# Power.net
KiCad netlist of a schematic drawn in Altium Designer
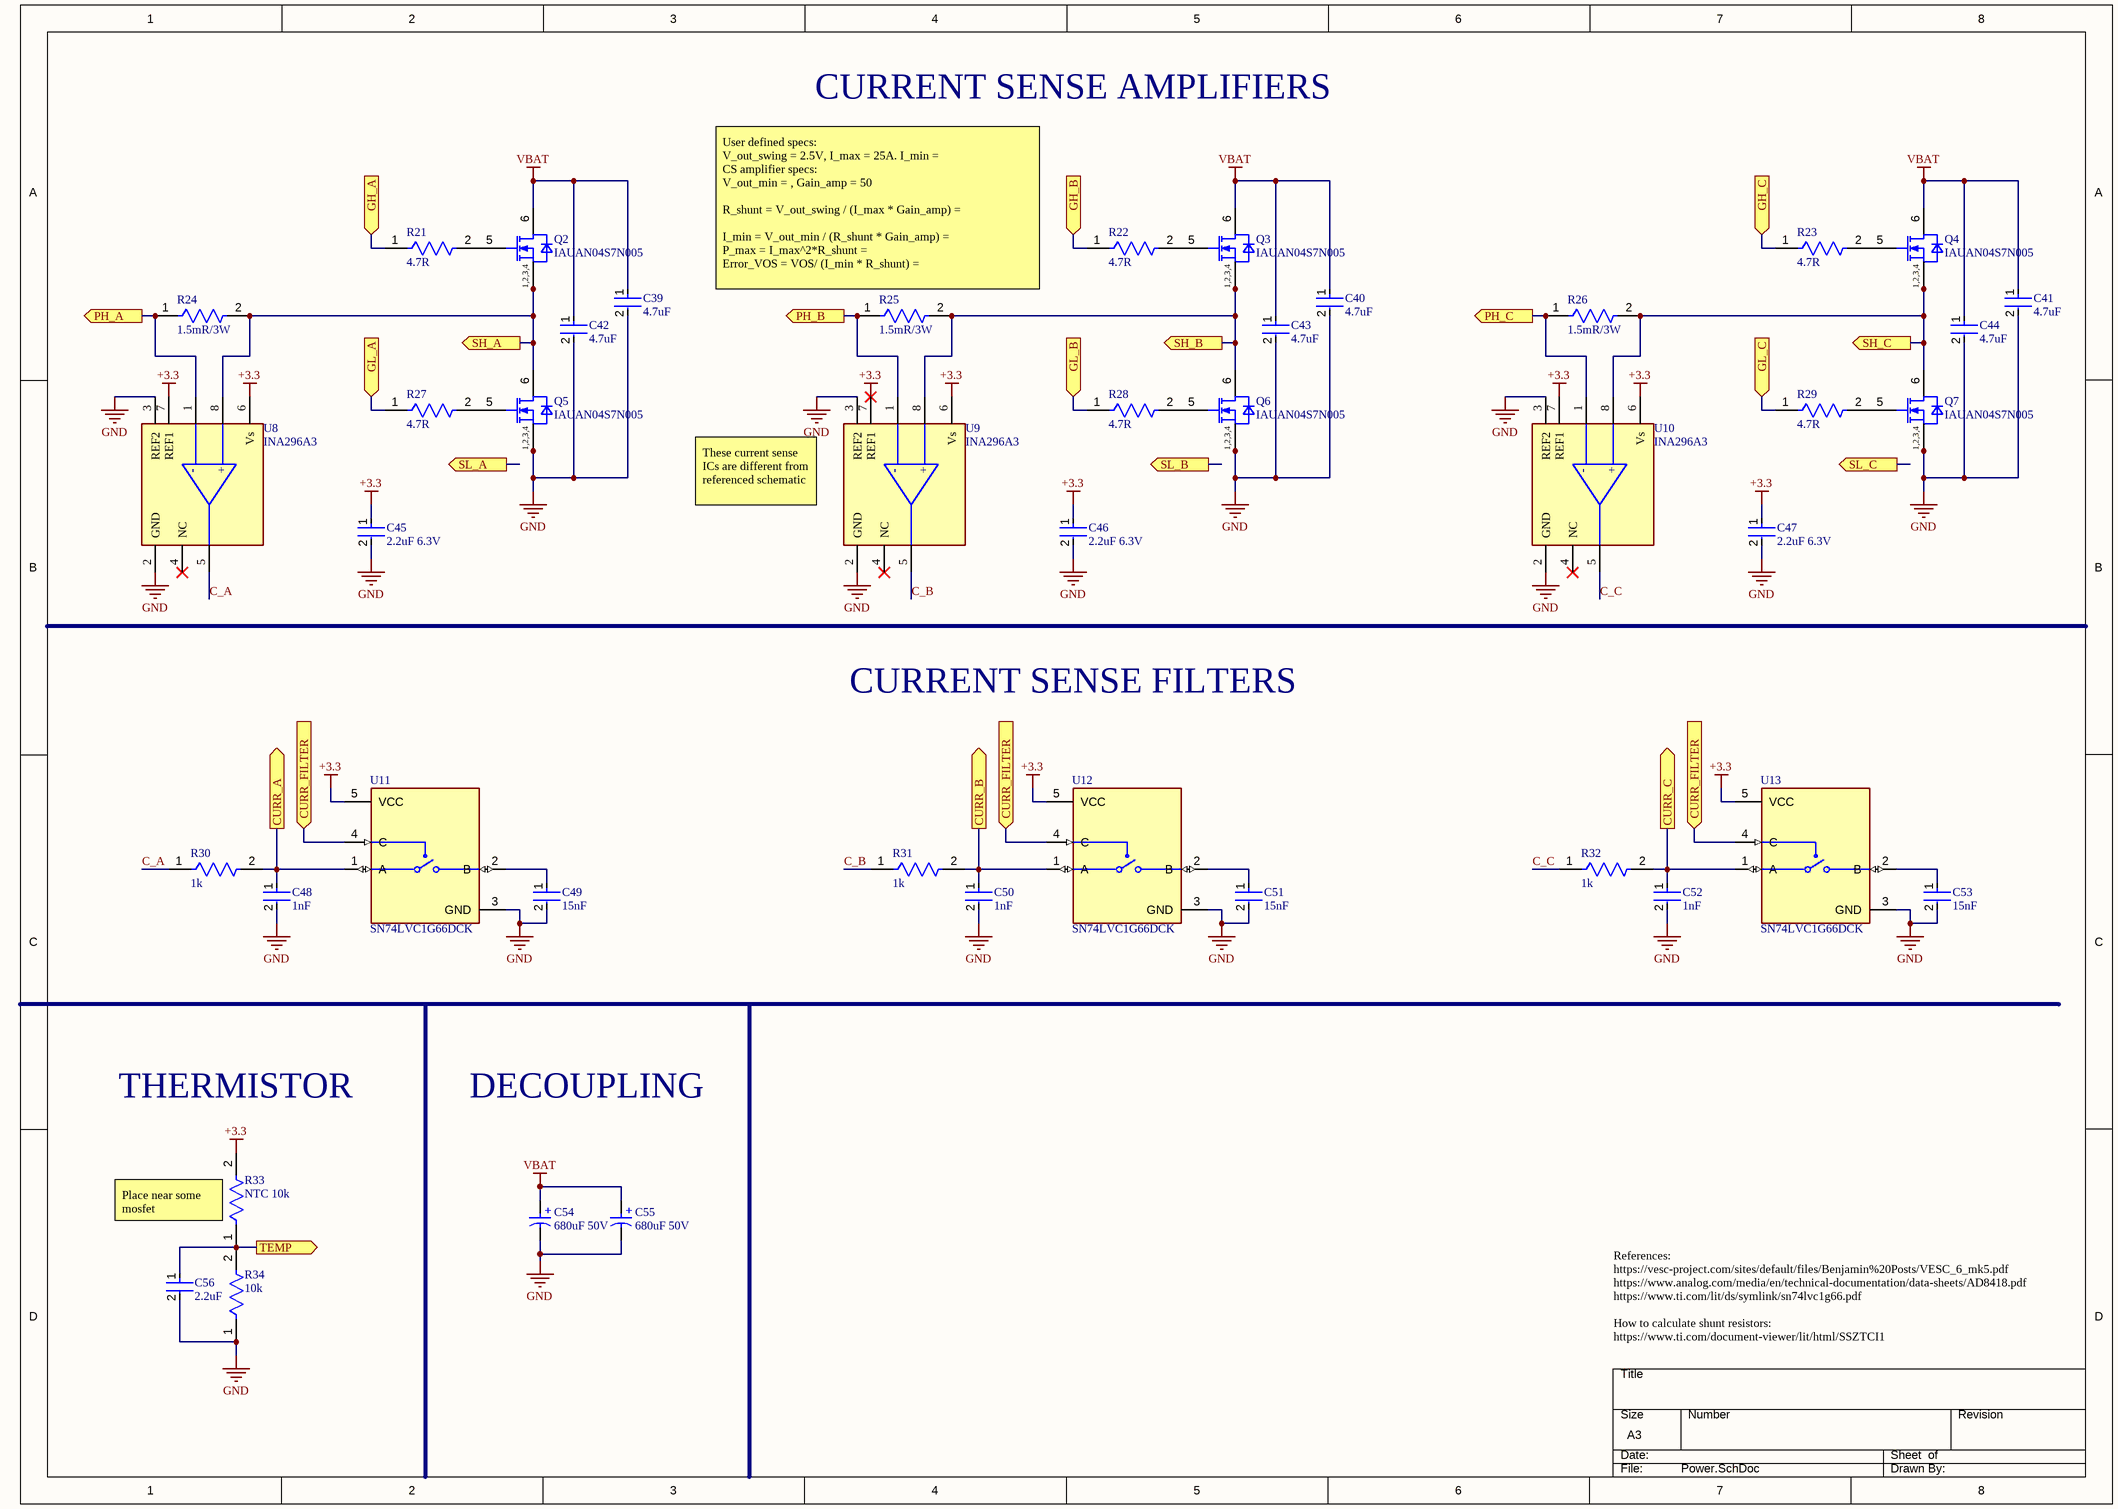
[diagram p0: Power.SchDoc]

(export (version "E")
  (design (tool "Eeschema 10.0.6"))
  (components
    (comp (ref "C39")
      (value "4.7uF")
      (footprint "FP-CC0805-0_85-MFG")
      (description "4.7uF 50V X7R ±10% 0805 Multilayer Ceramic Capacitors MLCC - SMD/SMT ROHS")
      (fields
        (field (name "MANUFACTURER") "Yageo Group")
        (field (name "MANUFACTURER PART NUMBER") "CC0402KRX7R9BB682")
      )
      (libsource (lib "BEESC_Lib") (part "0805B475K500NT"))
    )
    (comp (ref "C40")
      (value "4.7uF")
      (footprint "FP-CC0805-0_85-MFG")
      (description "4.7uF 50V X7R ±10% 0805 Multilayer Ceramic Capacitors MLCC - SMD/SMT ROHS")
      (fields
        (field (name "MANUFACTURER") "Yageo Group")
        (field (name "MANUFACTURER PART NUMBER") "CC0402KRX7R9BB682")
      )
      (libsource (lib "BEESC_Lib") (part "0805B475K500NT"))
    )
    (comp (ref "C41")
      (value "4.7uF")
      (footprint "FP-CC0805-0_85-MFG")
      (description "4.7uF 50V X7R ±10% 0805 Multilayer Ceramic Capacitors MLCC - SMD/SMT ROHS")
      (fields
        (field (name "MANUFACTURER") "Yageo Group")
        (field (name "MANUFACTURER PART NUMBER") "CC0402KRX7R9BB682")
      )
      (libsource (lib "BEESC_Lib") (part "0805B475K500NT"))
    )
    (comp (ref "C42")
      (value "4.7uF")
      (footprint "FP-CC0805-0_85-MFG")
      (description "4.7uF 50V X7R ±10% 0805 Multilayer Ceramic Capacitors MLCC - SMD/SMT ROHS")
      (fields
        (field (name "MANUFACTURER") "Yageo Group")
        (field (name "MANUFACTURER PART NUMBER") "CC0402KRX7R9BB682")
      )
      (libsource (lib "BEESC_Lib") (part "0805B475K500NT"))
    )
    (comp (ref "C43")
      (value "4.7uF")
      (footprint "FP-CC0805-0_85-MFG")
      (description "4.7uF 50V X7R ±10% 0805 Multilayer Ceramic Capacitors MLCC - SMD/SMT ROHS")
      (fields
        (field (name "MANUFACTURER") "Yageo Group")
        (field (name "MANUFACTURER PART NUMBER") "CC0402KRX7R9BB682")
      )
      (libsource (lib "BEESC_Lib") (part "0805B475K500NT"))
    )
    (comp (ref "C44")
      (value "4.7uF")
      (footprint "FP-CC0805-0_85-MFG")
      (description "4.7uF 50V X7R ±10% 0805 Multilayer Ceramic Capacitors MLCC - SMD/SMT ROHS")
      (fields
        (field (name "MANUFACTURER") "Yageo Group")
        (field (name "MANUFACTURER PART NUMBER") "CC0402KRX7R9BB682")
      )
      (libsource (lib "BEESC_Lib") (part "0805B475K500NT"))
    )
    (comp (ref "C45")
      (value "2.2uF 6.3V")
      (footprint "FP-CC0402-MFG")
      (description "2.2uF 6.3V X5R ±20% 0402 Multilayer Ceramic Capacitors MLCC - SMD/SMT ROHS")
      (fields
        (field (name "MANUFACTURER") "Yageo Group")
        (field (name "MANUFACTURER PART NUMBER") "CC0402KRX7R9BB682")
      )
      (libsource (lib "BEESC_Lib") (part "CL05A225MQ5NSNC"))
    )
    (comp (ref "C46")
      (value "2.2uF 6.3V")
      (footprint "FP-CC0402-MFG")
      (description "2.2uF 6.3V X5R ±20% 0402 Multilayer Ceramic Capacitors MLCC - SMD/SMT ROHS")
      (fields
        (field (name "MANUFACTURER") "Yageo Group")
        (field (name "MANUFACTURER PART NUMBER") "CC0402KRX7R9BB682")
      )
      (libsource (lib "BEESC_Lib") (part "CL05A225MQ5NSNC"))
    )
    (comp (ref "C47")
      (value "2.2uF 6.3V")
      (footprint "FP-CC0402-MFG")
      (description "2.2uF 6.3V X5R ±20% 0402 Multilayer Ceramic Capacitors MLCC - SMD/SMT ROHS")
      (fields
        (field (name "MANUFACTURER") "Yageo Group")
        (field (name "MANUFACTURER PART NUMBER") "CC0402KRX7R9BB682")
      )
      (libsource (lib "BEESC_Lib") (part "CL05A225MQ5NSNC"))
    )
    (comp (ref "C48")
      (value "1nF")
      (footprint "FP-CC0402-MFG")
      (description "1nF 50V X7R ±10% 0402 Multilayer Ceramic Capacitors MLCC - SMD/SMT ROHS")
      (fields
        (field (name "MANUFACTURER") "Yageo Group")
        (field (name "MANUFACTURER PART NUMBER") "CC0402KRX7R9BB682")
      )
      (libsource (lib "BEESC_Lib") (part "0402B102K500NT"))
    )
    (comp (ref "C49")
      (value "15nF")
      (footprint "FP-CC0402-MFG")
      (description "15nF 50V X7R ±10% 0402 Multilayer Ceramic Capacitors MLCC - SMD/SMT ROHS")
      (fields
        (field (name "MANUFACTURER") "Yageo Group")
        (field (name "MANUFACTURER PART NUMBER") "CC0402KRX7R9BB682")
      )
      (libsource (lib "BEESC_Lib") (part "CC0402KRX7R9BB153"))
    )
    (comp (ref "C50")
      (value "1nF")
      (footprint "FP-CC0402-MFG")
      (description "1nF 50V X7R ±10% 0402 Multilayer Ceramic Capacitors MLCC - SMD/SMT ROHS")
      (fields
        (field (name "MANUFACTURER") "Yageo Group")
        (field (name "MANUFACTURER PART NUMBER") "CC0402KRX7R9BB682")
      )
      (libsource (lib "BEESC_Lib") (part "0402B102K500NT"))
    )
    (comp (ref "C51")
      (value "15nF")
      (footprint "FP-CC0402-MFG")
      (description "15nF 50V X7R ±10% 0402 Multilayer Ceramic Capacitors MLCC - SMD/SMT ROHS")
      (fields
        (field (name "MANUFACTURER") "Yageo Group")
        (field (name "MANUFACTURER PART NUMBER") "CC0402KRX7R9BB682")
      )
      (libsource (lib "BEESC_Lib") (part "CC0402KRX7R9BB153"))
    )
    (comp (ref "C52")
      (value "1nF")
      (footprint "FP-CC0402-MFG")
      (description "1nF 50V X7R ±10% 0402 Multilayer Ceramic Capacitors MLCC - SMD/SMT ROHS")
      (fields
        (field (name "MANUFACTURER") "Yageo Group")
        (field (name "MANUFACTURER PART NUMBER") "CC0402KRX7R9BB682")
      )
      (libsource (lib "BEESC_Lib") (part "0402B102K500NT"))
    )
    (comp (ref "C53")
      (value "15nF")
      (footprint "FP-CC0402-MFG")
      (description "15nF 50V X7R ±10% 0402 Multilayer Ceramic Capacitors MLCC - SMD/SMT ROHS")
      (fields
        (field (name "MANUFACTURER") "Yageo Group")
        (field (name "MANUFACTURER PART NUMBER") "CC0402KRX7R9BB682")
      )
      (libsource (lib "BEESC_Lib") (part "CC0402KRX7R9BB153"))
    )
    (comp (ref "C54")
      (value "680uF 50V")
      (footprint "WCAP-ATG5_D13H20_BENT_MIRROR")
      (description "Aluminium Electrolytic Capacitors - Radial Leaded WCAP-ATG5 680uF 50V 20% Radial")
      (libsource (lib "BEESC_Lib") (part "860020678024"))
    )
    (comp (ref "C55")
      (value "680uF 50V")
      (footprint "WCAP-ATG5_D13H20_BENT_MIRROR")
      (description "Aluminium Electrolytic Capacitors - Radial Leaded WCAP-ATG5 680uF 50V 20% Radial")
      (libsource (lib "BEESC_Lib") (part "860020678024"))
    )
    (comp (ref "C56")
      (value "2.2uF")
      (footprint "FP-CC0805-0_85-MFG")
      (description "2.2uF 50V X7R ±10% 0805 Multilayer Ceramic Capacitors MLCC - SMD/SMT ROHS")
      (fields
        (field (name "MANUFACTURER") "Yageo Group")
        (field (name "MANUFACTURER PART NUMBER") "CC0402KRX7R9BB682")
      )
      (libsource (lib "BEESC_Lib") (part "CC0805KKX7R9BB225"))
    )
    (comp (ref "Q2")
      (value "IAUAN04S7N005")
      (footprint "IFX-PG-HSOF-5-1-V")
      (fields (field (name "MANUFACTURER") "Infineon Technologies"))
      (libsource (lib "BEESC_Lib") (part "IAUAN04S7N005"))
    )
    (comp (ref "Q3")
      (value "IAUAN04S7N005")
      (footprint "IFX-PG-HSOF-5-1-V")
      (fields (field (name "MANUFACTURER") "Infineon Technologies"))
      (libsource (lib "BEESC_Lib") (part "IAUAN04S7N005"))
    )
    (comp (ref "Q4")
      (value "IAUAN04S7N005")
      (footprint "IFX-PG-HSOF-5-1-V")
      (fields (field (name "MANUFACTURER") "Infineon Technologies"))
      (libsource (lib "BEESC_Lib") (part "IAUAN04S7N005"))
    )
    (comp (ref "Q5")
      (value "IAUAN04S7N005")
      (footprint "IFX-PG-HSOF-5-1-V")
      (fields (field (name "MANUFACTURER") "Infineon Technologies"))
      (libsource (lib "BEESC_Lib") (part "IAUAN04S7N005"))
    )
    (comp (ref "Q6")
      (value "IAUAN04S7N005")
      (footprint "IFX-PG-HSOF-5-1-V")
      (fields (field (name "MANUFACTURER") "Infineon Technologies"))
      (libsource (lib "BEESC_Lib") (part "IAUAN04S7N005"))
    )
    (comp (ref "Q7")
      (value "IAUAN04S7N005")
      (footprint "IFX-PG-HSOF-5-1-V")
      (fields (field (name "MANUFACTURER") "Infineon Technologies"))
      (libsource (lib "BEESC_Lib") (part "IAUAN04S7N005"))
    )
    (comp (ref "R21")
      (value "4.7R")
      (footprint "FP-AC0402-MFG")
      (libsource (lib "BEESC_Lib") (part "0402WGF470KTCE"))
    )
    (comp (ref "R22")
      (value "4.7R")
      (footprint "FP-AC0402-MFG")
      (libsource (lib "BEESC_Lib") (part "0402WGF470KTCE"))
    )
    (comp (ref "R23")
      (value "4.7R")
      (footprint "FP-AC0402-MFG")
      (libsource (lib "BEESC_Lib") (part "0402WGF470KTCE"))
    )
    (comp (ref "R24")
      (value "1.5mR/3W")
      (footprint "FP-AC2512-MFG")
      (libsource (lib "BEESC_Lib") (part "HoCGX2512-3W-1.5mR-1%"))
    )
    (comp (ref "R25")
      (value "1.5mR/3W")
      (footprint "FP-AC2512-MFG")
      (libsource (lib "BEESC_Lib") (part "HoCGX2512-3W-1.5mR-1%"))
    )
    (comp (ref "R26")
      (value "1.5mR/3W")
      (footprint "FP-AC2512-MFG")
      (libsource (lib "BEESC_Lib") (part "HoCGX2512-3W-1.5mR-1%"))
    )
    (comp (ref "R27")
      (value "4.7R")
      (footprint "FP-AC0402-MFG")
      (libsource (lib "BEESC_Lib") (part "0402WGF470KTCE"))
    )
    (comp (ref "R28")
      (value "4.7R")
      (footprint "FP-AC0402-MFG")
      (libsource (lib "BEESC_Lib") (part "0402WGF470KTCE"))
    )
    (comp (ref "R29")
      (value "4.7R")
      (footprint "FP-AC0402-MFG")
      (libsource (lib "BEESC_Lib") (part "0402WGF470KTCE"))
    )
    (comp (ref "R30")
      (value "1k")
      (footprint "FP-AC0402-MFG")
      (libsource (lib "BEESC_Lib") (part "0402WGF1001TCE"))
    )
    (comp (ref "R31")
      (value "1k")
      (footprint "FP-AC0402-MFG")
      (libsource (lib "BEESC_Lib") (part "0402WGF1001TCE"))
    )
    (comp (ref "R32")
      (value "1k")
      (footprint "FP-AC0402-MFG")
      (libsource (lib "BEESC_Lib") (part "0402WGF1001TCE"))
    )
    (comp (ref "R33")
      (value "NTC 10k")
      (footprint "FP-AC0402-MFG")
      (description "-40℃~+125℃ 0.5mm 100mW 10kΩ 1mW/℃ 1mm 310uA 3380K 3434K 3455K ±1% ±1% 0402 NTC Thermistors ROHS")
      (libsource (lib "BEESC_Lib") (part "NCP15XH103F03RC"))
    )
    (comp (ref "R34")
      (value "10k")
      (footprint "FP-AC0402-MFG")
      (libsource (lib "BEESC_Lib") (part "0402WGF1002TCE"))
    )
    (comp (ref "U8")
      (value "INA296A3")
      (footprint "FP-DDF0008A-MFG")
      (libsource (lib "BEESC_Lib") (part "INA296A3IDDFR"))
    )
    (comp (ref "U9")
      (value "INA296A3")
      (footprint "FP-DDF0008A-MFG")
      (libsource (lib "BEESC_Lib") (part "INA296A3IDDFR"))
    )
    (comp (ref "U10")
      (value "INA296A3")
      (footprint "FP-DDF0008A-MFG")
      (libsource (lib "BEESC_Lib") (part "INA296A3IDDFR"))
    )
    (comp (ref "U11")
      (value "SN74LVC1G66DCK")
      (footprint "FP-DCK0005A-MFG")
      (libsource (lib "BEESC_Lib") (part "SN74LVC1G66DCKR"))
    )
    (comp (ref "U12")
      (value "SN74LVC1G66DCK")
      (footprint "FP-DCK0005A-MFG")
      (libsource (lib "BEESC_Lib") (part "SN74LVC1G66DCKR"))
    )
    (comp (ref "U13")
      (value "SN74LVC1G66DCK")
      (footprint "FP-DCK0005A-MFG")
      (libsource (lib "BEESC_Lib") (part "SN74LVC1G66DCKR"))
    )
  )
  (nets
    (net (code "1") (name "+3.3") (class "Default")
      (node (ref "C45") (pin "1") (pinfunction "1_1") (pintype "passive"))
      (node (ref "C46") (pin "1") (pinfunction "1_1") (pintype "passive"))
      (node (ref "C47") (pin "1") (pinfunction "1_1") (pintype "passive"))
      (node (ref "R33") (pin "2") (pinfunction "2_2") (pintype "passive"))
      (node (ref "U10") (pin "6") (pinfunction "Vs_6") (pintype "power_in"))
      (node (ref "U10") (pin "7") (pinfunction "REF1_7") (pintype "passive"))
      (node (ref "U11") (pin "5") (pinfunction "VCC_5") (pintype "power_in"))
      (node (ref "U12") (pin "5") (pinfunction "VCC_5") (pintype "power_in"))
      (node (ref "U13") (pin "5") (pinfunction "VCC_5") (pintype "power_in"))
      (node (ref "U8") (pin "6") (pinfunction "Vs_6") (pintype "power_in"))
      (node (ref "U8") (pin "7") (pinfunction "REF1_7") (pintype "passive"))
      (node (ref "U9") (pin "6") (pinfunction "Vs_6") (pintype "power_in"))
      (node (ref "U9") (pin "7") (pinfunction "REF1_7") (pintype "passive"))
    )
    (net (code "2") (name "/CURR_A") (class "Default")
      (node (ref "C48") (pin "1") (pinfunction "1_1") (pintype "passive"))
      (node (ref "R30") (pin "2") (pinfunction "2_2") (pintype "passive"))
      (node (ref "U11") (pin "1") (pinfunction "A_1") (pintype "bidirectional"))
    )
    (net (code "3") (name "/CURR_B") (class "Default")
      (node (ref "C50") (pin "1") (pinfunction "1_1") (pintype "passive"))
      (node (ref "R31") (pin "2") (pinfunction "2_2") (pintype "passive"))
      (node (ref "U12") (pin "1") (pinfunction "A_1") (pintype "bidirectional"))
    )
    (net (code "4") (name "/CURR_C") (class "Default")
      (node (ref "C52") (pin "1") (pinfunction "1_1") (pintype "passive"))
      (node (ref "R32") (pin "2") (pinfunction "2_2") (pintype "passive"))
      (node (ref "U13") (pin "1") (pinfunction "A_1") (pintype "bidirectional"))
    )
    (net (code "5") (name "/CURR_FILTER") (class "Default")
      (node (ref "U11") (pin "4") (pinfunction "C_4") (pintype "input"))
      (node (ref "U12") (pin "4") (pinfunction "C_4") (pintype "input"))
      (node (ref "U13") (pin "4") (pinfunction "C_4") (pintype "input"))
    )
    (net (code "6") (name "/C_A") (class "Default")
      (node (ref "R30") (pin "1") (pinfunction "1_1") (pintype "passive"))
      (node (ref "U8") (pin "5") (pinfunction "OUT_5") (pintype "passive"))
    )
    (net (code "7") (name "/C_B") (class "Default")
      (node (ref "R31") (pin "1") (pinfunction "1_1") (pintype "passive"))
      (node (ref "U9") (pin "5") (pinfunction "OUT_5") (pintype "passive"))
    )
    (net (code "8") (name "/C_C") (class "Default")
      (node (ref "R32") (pin "1") (pinfunction "1_1") (pintype "passive"))
      (node (ref "U10") (pin "5") (pinfunction "OUT_5") (pintype "passive"))
    )
    (net (code "9") (name "/GH_A") (class "Default")
      (node (ref "R21") (pin "1") (pinfunction "1_1") (pintype "passive"))
    )
    (net (code "10") (name "/GH_B") (class "Default")
      (node (ref "R22") (pin "1") (pinfunction "1_1") (pintype "passive"))
    )
    (net (code "11") (name "/GH_C") (class "Default")
      (node (ref "R23") (pin "1") (pinfunction "1_1") (pintype "passive"))
    )
    (net (code "12") (name "/GL_A") (class "Default")
      (node (ref "R27") (pin "1") (pinfunction "1_1") (pintype "passive"))
    )
    (net (code "13") (name "/GL_B") (class "Default")
      (node (ref "R28") (pin "1") (pinfunction "1_1") (pintype "passive"))
    )
    (net (code "14") (name "/GL_C") (class "Default")
      (node (ref "R29") (pin "1") (pinfunction "1_1") (pintype "passive"))
    )
    (net (code "15") (name "/PH_A") (class "Default")
      (node (ref "R24") (pin "1") (pinfunction "1_1") (pintype "passive"))
      (node (ref "U8") (pin "1") (pinfunction "IN-_1") (pintype "tri_state"))
    )
    (net (code "16") (name "/PH_B") (class "Default")
      (node (ref "R25") (pin "1") (pinfunction "1_1") (pintype "passive"))
      (node (ref "U9") (pin "1") (pinfunction "IN-_1") (pintype "tri_state"))
    )
    (net (code "17") (name "/PH_C") (class "Default")
      (node (ref "R26") (pin "1") (pinfunction "1_1") (pintype "passive"))
      (node (ref "U10") (pin "1") (pinfunction "IN-_1") (pintype "tri_state"))
    )
    (net (code "18") (name "/SH_A") (class "Default")
      (node (ref "Q2") (pin "1") (pinfunction "S1_1") (pintype "passive"))
      (node (ref "Q2") (pin "2") (pinfunction "S2_2") (pintype "passive"))
      (node (ref "Q2") (pin "3") (pinfunction "S3_3") (pintype "passive"))
      (node (ref "Q2") (pin "4") (pinfunction "S4_4") (pintype "passive"))
      (node (ref "Q5") (pin "6") (pinfunction "D_6") (pintype "passive"))
      (node (ref "R24") (pin "2") (pinfunction "2_2") (pintype "passive"))
      (node (ref "U8") (pin "8") (pinfunction "IN+_8") (pintype "tri_state"))
    )
    (net (code "19") (name "/SH_B") (class "Default")
      (node (ref "Q3") (pin "1") (pinfunction "S1_1") (pintype "passive"))
      (node (ref "Q3") (pin "2") (pinfunction "S2_2") (pintype "passive"))
      (node (ref "Q3") (pin "3") (pinfunction "S3_3") (pintype "passive"))
      (node (ref "Q3") (pin "4") (pinfunction "S4_4") (pintype "passive"))
      (node (ref "Q6") (pin "6") (pinfunction "D_6") (pintype "passive"))
      (node (ref "R25") (pin "2") (pinfunction "2_2") (pintype "passive"))
      (node (ref "U9") (pin "8") (pinfunction "IN+_8") (pintype "tri_state"))
    )
    (net (code "20") (name "/SH_C") (class "Default")
      (node (ref "Q4") (pin "1") (pinfunction "S1_1") (pintype "passive"))
      (node (ref "Q4") (pin "2") (pinfunction "S2_2") (pintype "passive"))
      (node (ref "Q4") (pin "3") (pinfunction "S3_3") (pintype "passive"))
      (node (ref "Q4") (pin "4") (pinfunction "S4_4") (pintype "passive"))
      (node (ref "Q7") (pin "6") (pinfunction "D_6") (pintype "passive"))
      (node (ref "R26") (pin "2") (pinfunction "2_2") (pintype "passive"))
      (node (ref "U10") (pin "8") (pinfunction "IN+_8") (pintype "tri_state"))
    )
    (net (code "24") (name "/TEMP") (class "Default")
      (node (ref "C56") (pin "1") (pinfunction "1_1") (pintype "passive"))
      (node (ref "R33") (pin "1") (pinfunction "1_1") (pintype "passive"))
      (node (ref "R34") (pin "2") (pinfunction "2_2") (pintype "passive"))
    )
    (net (code "25") (name "GND") (class "Default")
      (node (ref "C39") (pin "2") (pinfunction "2_2") (pintype "passive"))
      (node (ref "C40") (pin "2") (pinfunction "2_2") (pintype "passive"))
      (node (ref "C41") (pin "2") (pinfunction "2_2") (pintype "passive"))
      (node (ref "C42") (pin "2") (pinfunction "2_2") (pintype "passive"))
      (node (ref "C43") (pin "2") (pinfunction "2_2") (pintype "passive"))
      (node (ref "C44") (pin "2") (pinfunction "2_2") (pintype "passive"))
      (node (ref "C45") (pin "2") (pinfunction "2_2") (pintype "passive"))
      (node (ref "C46") (pin "2") (pinfunction "2_2") (pintype "passive"))
      (node (ref "C47") (pin "2") (pinfunction "2_2") (pintype "passive"))
      (node (ref "C48") (pin "2") (pinfunction "2_2") (pintype "passive"))
      (node (ref "C49") (pin "2") (pinfunction "2_2") (pintype "passive"))
      (node (ref "C50") (pin "2") (pinfunction "2_2") (pintype "passive"))
      (node (ref "C51") (pin "2") (pinfunction "2_2") (pintype "passive"))
      (node (ref "C52") (pin "2") (pinfunction "2_2") (pintype "passive"))
      (node (ref "C53") (pin "2") (pinfunction "2_2") (pintype "passive"))
      (node (ref "C54") (pin "2") (pinfunction "N_2") (pintype "passive"))
      (node (ref "C55") (pin "2") (pinfunction "N_2") (pintype "passive"))
      (node (ref "C56") (pin "2") (pinfunction "2_2") (pintype "passive"))
      (node (ref "Q5") (pin "1") (pinfunction "S1_1") (pintype "passive"))
      (node (ref "Q5") (pin "2") (pinfunction "S2_2") (pintype "passive"))
      (node (ref "Q5") (pin "3") (pinfunction "S3_3") (pintype "passive"))
      (node (ref "Q5") (pin "4") (pinfunction "S4_4") (pintype "passive"))
      (node (ref "Q6") (pin "1") (pinfunction "S1_1") (pintype "passive"))
      (node (ref "Q6") (pin "2") (pinfunction "S2_2") (pintype "passive"))
      (node (ref "Q6") (pin "3") (pinfunction "S3_3") (pintype "passive"))
      (node (ref "Q6") (pin "4") (pinfunction "S4_4") (pintype "passive"))
      (node (ref "Q7") (pin "1") (pinfunction "S1_1") (pintype "passive"))
      (node (ref "Q7") (pin "2") (pinfunction "S2_2") (pintype "passive"))
      (node (ref "Q7") (pin "3") (pinfunction "S3_3") (pintype "passive"))
      (node (ref "Q7") (pin "4") (pinfunction "S4_4") (pintype "passive"))
      (node (ref "R34") (pin "1") (pinfunction "1_1") (pintype "passive"))
      (node (ref "U10") (pin "2") (pinfunction "GND_2") (pintype "power_in"))
      (node (ref "U10") (pin "3") (pinfunction "REF2_3") (pintype "passive"))
      (node (ref "U11") (pin "3") (pinfunction "GND_3") (pintype "power_in"))
      (node (ref "U12") (pin "3") (pinfunction "GND_3") (pintype "power_in"))
      (node (ref "U13") (pin "3") (pinfunction "GND_3") (pintype "power_in"))
      (node (ref "U8") (pin "2") (pinfunction "GND_2") (pintype "power_in"))
      (node (ref "U8") (pin "3") (pinfunction "REF2_3") (pintype "passive"))
      (node (ref "U9") (pin "2") (pinfunction "GND_2") (pintype "power_in"))
      (node (ref "U9") (pin "3") (pinfunction "REF2_3") (pintype "passive"))
    )
    (net (code "26") (name "Net-(Q2-G)") (class "Default")
      (node (ref "Q2") (pin "5") (pinfunction "G_5") (pintype "passive"))
      (node (ref "R21") (pin "2") (pinfunction "2_2") (pintype "passive"))
    )
    (net (code "27") (name "Net-(Q3-G)") (class "Default")
      (node (ref "Q3") (pin "5") (pinfunction "G_5") (pintype "passive"))
      (node (ref "R22") (pin "2") (pinfunction "2_2") (pintype "passive"))
    )
    (net (code "28") (name "Net-(Q4-G)") (class "Default")
      (node (ref "Q4") (pin "5") (pinfunction "G_5") (pintype "passive"))
      (node (ref "R23") (pin "2") (pinfunction "2_2") (pintype "passive"))
    )
    (net (code "29") (name "Net-(Q5-G)") (class "Default")
      (node (ref "Q5") (pin "5") (pinfunction "G_5") (pintype "passive"))
      (node (ref "R27") (pin "2") (pinfunction "2_2") (pintype "passive"))
    )
    (net (code "30") (name "Net-(Q6-G)") (class "Default")
      (node (ref "Q6") (pin "5") (pinfunction "G_5") (pintype "passive"))
      (node (ref "R28") (pin "2") (pinfunction "2_2") (pintype "passive"))
    )
    (net (code "31") (name "Net-(Q7-G)") (class "Default")
      (node (ref "Q7") (pin "5") (pinfunction "G_5") (pintype "passive"))
      (node (ref "R29") (pin "2") (pinfunction "2_2") (pintype "passive"))
    )
    (net (code "32") (name "Net-(U11-B)") (class "Default")
      (node (ref "C49") (pin "1") (pinfunction "1_1") (pintype "passive"))
      (node (ref "U11") (pin "2") (pinfunction "B_2") (pintype "bidirectional"))
    )
    (net (code "33") (name "Net-(U12-B)") (class "Default")
      (node (ref "C51") (pin "1") (pinfunction "1_1") (pintype "passive"))
      (node (ref "U12") (pin "2") (pinfunction "B_2") (pintype "bidirectional"))
    )
    (net (code "34") (name "Net-(U13-B)") (class "Default")
      (node (ref "C53") (pin "1") (pinfunction "1_1") (pintype "passive"))
      (node (ref "U13") (pin "2") (pinfunction "B_2") (pintype "bidirectional"))
    )
    (net (code "35") (name "VBAT") (class "Default")
      (node (ref "C39") (pin "1") (pinfunction "1_1") (pintype "passive"))
      (node (ref "C40") (pin "1") (pinfunction "1_1") (pintype "passive"))
      (node (ref "C41") (pin "1") (pinfunction "1_1") (pintype "passive"))
      (node (ref "C42") (pin "1") (pinfunction "1_1") (pintype "passive"))
      (node (ref "C43") (pin "1") (pinfunction "1_1") (pintype "passive"))
      (node (ref "C44") (pin "1") (pinfunction "1_1") (pintype "passive"))
      (node (ref "C54") (pin "1") (pinfunction "P_1") (pintype "passive"))
      (node (ref "C55") (pin "1") (pinfunction "P_1") (pintype "passive"))
      (node (ref "Q2") (pin "6") (pinfunction "D_6") (pintype "passive"))
      (node (ref "Q3") (pin "6") (pinfunction "D_6") (pintype "passive"))
      (node (ref "Q4") (pin "6") (pinfunction "D_6") (pintype "passive"))
    )
    (net (code "36") (name "unconnected-(U8-NC-Pad4)") (class "Default")
      (node (ref "U8") (pin "4") (pinfunction "NC_4") (pintype "passive+no_connect"))
    )
    (net (code "37") (name "unconnected-(U9-NC-Pad4)") (class "Default")
      (node (ref "U9") (pin "4") (pinfunction "NC_4") (pintype "passive+no_connect"))
    )
    (net (code "38") (name "unconnected-(U10-NC-Pad4)") (class "Default")
      (node (ref "U10") (pin "4") (pinfunction "NC_4") (pintype "passive+no_connect"))
    )
  )
)
